# DevelopmentBoard_08M2.net
KiCad netlist of a schematic drawn in EAGLE
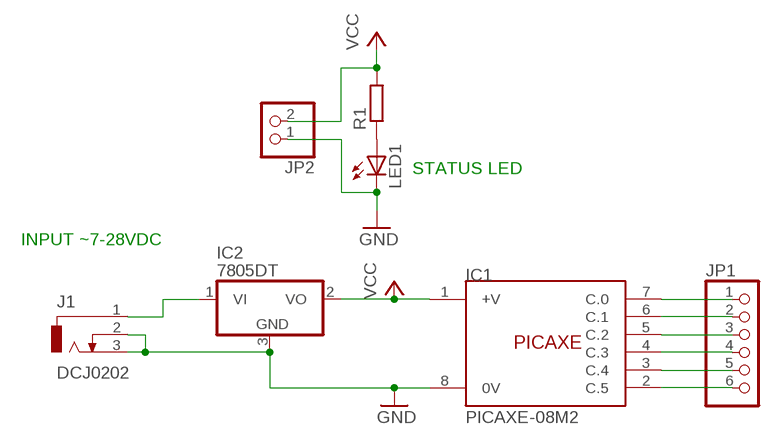
[diagram p0: schematic, sheet 1]

(export (version "E")
  (design (tool "Eeschema 10.0.6"))
  (components
    (comp (ref "IC1")
      (value "PICAXE-08M2")
      (footprint "eagle-import:SOIC8")
      (libsource (lib "eagle-import") (part "PICAXE-08M2"))
    )
    (comp (ref "IC2")
      (value "7805DT")
      (footprint "eagle-import:TO252")
      (libsource (lib "eagle-import") (part "78DT05"))
    )
    (comp (ref "J1")
      (value "DCJ0202")
      (footprint "eagle-import:DCJ0202")
      (libsource (lib "eagle-import") (part "DCJ0202"))
    )
    (comp (ref "JP1")
      (value "PINHD-1X6")
      (footprint "eagle-import:1X06")
      (libsource (lib "eagle-import") (part "PINHD-1X6"))
    )
    (comp (ref "JP2")
      (value "PINHD-1X2")
      (footprint "eagle-import:1X02")
      (libsource (lib "eagle-import") (part "PINHD-1X2"))
    )
    (comp (ref "LED1")
      (value "LEDCHIPLED_1206")
      (footprint "eagle-import:CHIPLED_1206")
      (libsource (lib "eagle-import") (part "LEDCHIPLED_1206"))
    )
    (comp (ref "R1")
      (value "R-EU_R1206")
      (footprint "eagle-import:R1206")
      (libsource (lib "eagle-import") (part "R-EU_R1206"))
    )
  )
  (nets
    (net (code "1") (name "GND") (class "Default")
      (node (ref "IC1") (pin "8") (pinfunction "0V_8") (pintype "power_in"))
      (node (ref "IC2") (pin "3") (pinfunction "GND_3") (pintype "passive"))
      (node (ref "J1") (pin "2") (pinfunction "2_2") (pintype "passive"))
      (node (ref "J1") (pin "3") (pinfunction "3_3") (pintype "passive"))
      (node (ref "JP2") (pin "1") (pinfunction "1_1") (pintype "passive"))
      (node (ref "LED1") (pin "C") (pinfunction "C_C") (pintype "passive"))
    )
    (net (code "2") (name "Net-(IC1-C.0)") (class "Default")
      (node (ref "IC1") (pin "7") (pinfunction "C.0_7") (pintype "bidirectional"))
      (node (ref "JP1") (pin "1") (pinfunction "1_1") (pintype "passive"))
    )
    (net (code "3") (name "Net-(IC1-C.1)") (class "Default")
      (node (ref "IC1") (pin "6") (pinfunction "C.1_6") (pintype "bidirectional"))
      (node (ref "JP1") (pin "2") (pinfunction "2_2") (pintype "passive"))
    )
    (net (code "4") (name "Net-(IC1-C.2)") (class "Default")
      (node (ref "IC1") (pin "5") (pinfunction "C.2_5") (pintype "bidirectional"))
      (node (ref "JP1") (pin "3") (pinfunction "3_3") (pintype "passive"))
    )
    (net (code "5") (name "Net-(IC1-C.3)") (class "Default")
      (node (ref "IC1") (pin "4") (pinfunction "C.3_4") (pintype "bidirectional"))
      (node (ref "JP1") (pin "4") (pinfunction "4_4") (pintype "passive"))
    )
    (net (code "6") (name "Net-(IC1-C.4)") (class "Default")
      (node (ref "IC1") (pin "3") (pinfunction "C.4_3") (pintype "bidirectional"))
      (node (ref "JP1") (pin "5") (pinfunction "5_5") (pintype "passive"))
    )
    (net (code "7") (name "Net-(IC1-C.5)") (class "Default")
      (node (ref "IC1") (pin "2") (pinfunction "C.5_2") (pintype "bidirectional"))
      (node (ref "JP1") (pin "6") (pinfunction "6_6") (pintype "passive"))
    )
    (net (code "8") (name "Net-(IC2-VI)") (class "Default")
      (node (ref "IC2") (pin "1") (pinfunction "VI_1") (pintype "input"))
      (node (ref "J1") (pin "1") (pinfunction "1_1") (pintype "passive"))
    )
    (net (code "9") (name "Net-(LED1-PadA)") (class "Default")
      (node (ref "LED1") (pin "A") (pinfunction "A_A") (pintype "passive"))
      (node (ref "R1") (pin "1") (pinfunction "1_1") (pintype "passive"))
    )
    (net (code "10") (name "VCC") (class "Default")
      (node (ref "IC1") (pin "1") (pinfunction "+V_1") (pintype "power_in"))
      (node (ref "IC2") (pin "2") (pinfunction "VO_2") (pintype "passive"))
      (node (ref "JP2") (pin "2") (pinfunction "2_2") (pintype "passive"))
      (node (ref "R1") (pin "2") (pinfunction "2_2") (pintype "passive"))
    )
  )
)
